# PowerSupply.net
KiCad netlist of a schematic drawn in Altium Designer
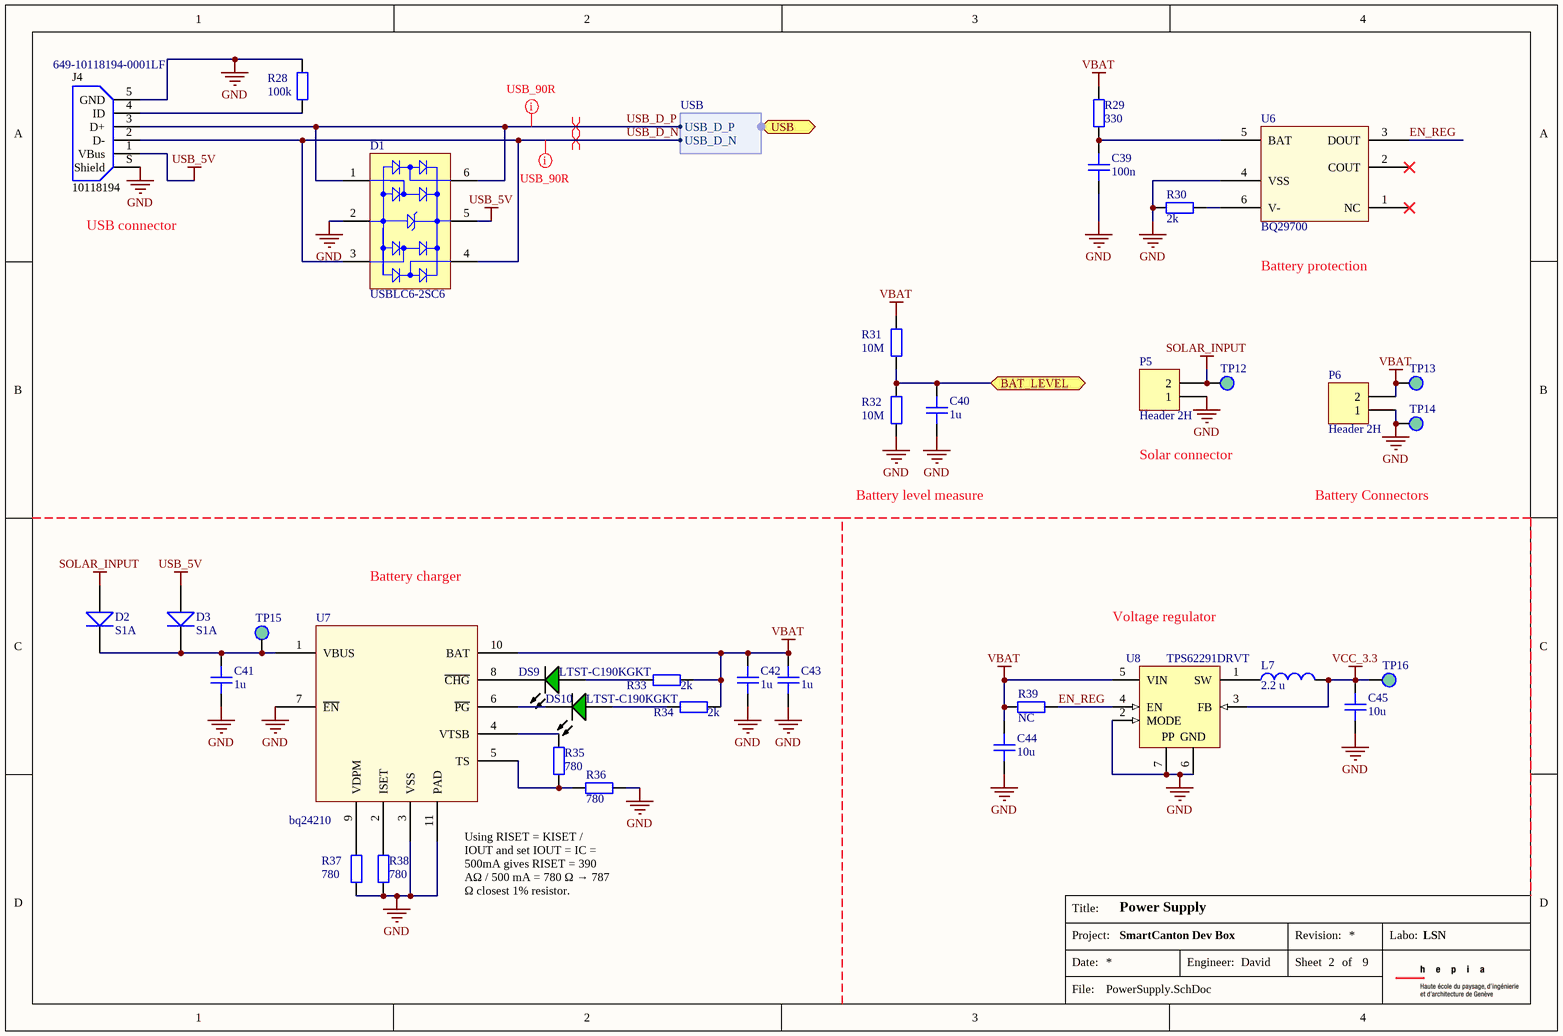
[diagram p0: PowerSupply.SchDoc]

(export (version "E")
  (design (tool "Eeschema 10.0.6"))
  (components
    (comp (ref "C39")
      (value "100n")
      (footprint "CAPC1608X08")
      (description "MLCC Capacitor 1608")
      (libsource (lib "HEPIA Vault") (part "CMP-001-0010-A.3"))
    )
    (comp (ref "C40")
      (value "1u")
      (footprint "CAPC1608X08")
      (description "MLCC Capacitor 1608")
      (libsource (lib "HEPIA Vault") (part "CMP-001-0010-A.3"))
    )
    (comp (ref "C41")
      (value "1u")
      (footprint "CAPC1608X08")
      (description "MLCC Capacitor 1608")
      (libsource (lib "HEPIA Vault") (part "CMP-001-0010-A.3"))
    )
    (comp (ref "C42")
      (value "1u")
      (footprint "CAPC1608X08")
      (description "MLCC Capacitor 1608")
      (libsource (lib "HEPIA Vault") (part "CMP-001-0010-A.3"))
    )
    (comp (ref "C43")
      (value "1u")
      (footprint "CAPC1608X08")
      (description "MLCC Capacitor 1608")
      (libsource (lib "HEPIA Vault") (part "CMP-001-0010-A.3"))
    )
    (comp (ref "C44")
      (value "10u")
      (footprint "CAPC2012X14")
      (description "MLCC Capacitor 2012")
      (libsource (lib "HEPIA Vault") (part "CMP-001-0011-A.3"))
    )
    (comp (ref "C45")
      (value "10u")
      (footprint "CAPC2012X14")
      (description "MLCC Capacitor 2012")
      (libsource (lib "HEPIA Vault") (part "CMP-001-0011-A.3"))
    )
    (comp (ref "D1")
      (value "USBLC6-2SC6")
      (footprint "STM-SOT23-6L_V")
      (description "Very low capacitance ESD protection, 3.5 pF, -40 to 125 degC, 6-Pin SOT23, RoHS, Tape and Reel")
      (fields (field (name "MANUFACTURER") "STMicroelectronics"))
      (libsource (lib "Altium Content Vault") (part "STM-USB_DVI_HDMIULC6-4SC6X-SOT23-6L"))
    )
    (comp (ref "D2")
      (value "S1A")
      (footprint "DO-214AC")
      (description "General-Purpose Rectifier, Vrrm = 50V")
      (libsource (lib "HEPIA Vault") (part "Diode"))
    )
    (comp (ref "D3")
      (value "S1A")
      (footprint "DO-214AC")
      (description "General-Purpose Rectifier, Vrrm = 50V")
      (libsource (lib "HEPIA Vault") (part "Diode"))
    )
    (comp (ref "DS9")
      (value "LTST-C190KGKT")
      (footprint "LITE-ON-LTST-C190GKT-2_V")
      (description "LED Uni-Color Green, 75 mW, 5 V, -30 to 85 degC, 2-Pin SMD, RoHS, Tape and Reel")
      (fields (field (name "MANUFACTURER") "Lite-On"))
      (libsource (lib "HEPIA Vault") (part "CMP-00026-A.1"))
    )
    (comp (ref "DS10")
      (value "LTST-C190KGKT")
      (footprint "LITE-ON-LTST-C190GKT-2_V")
      (description "LED Uni-Color Green, 75 mW, 5 V, -30 to 85 degC, 2-Pin SMD, RoHS, Tape and Reel")
      (fields (field (name "MANUFACTURER") "Lite-On"))
      (libsource (lib "HEPIA Vault") (part "LED_GREEN_A1K2-2"))
    )
    (comp (ref "J4")
      (value "10118194")
      (footprint "10118194-0001LF")
      (fields (field (name "SUPPLIER PART NUMBER 1") "649-10118194-0001LF"))
      (libsource (lib "HEPIA Vault") (part "CMP-001-0075-A.1"))
    )
    (comp (ref "L7")
      (value "2.2 u")
      (footprint "TDK-IND0805-125_V")
      (description "Multilayer Inductor, 2.2 uH, ±20%, 300 mOhm, 50MHz, 0805(2012)")
      (fields (field (name "PARTNUMBER") "MLZ2012N100LT"))
      (libsource (lib "Altium Content Vault") (part "CMP-0266-00001-1"))
    )
    (comp (ref "P5")
      (value "Header 2H")
      (footprint "HDR1X2H")
      (description "Header, 2-Pin, Right Angle")
      (fields (field (name "PUBLISHER") "Altium Limited"))
      (libsource (lib "Miscellaneous Connectors") (part "Header 2H"))
    )
    (comp (ref "P6")
      (value "Header 2H")
      (footprint "HDR1X2H")
      (description "Header, 2-Pin, Right Angle")
      (fields (field (name "PUBLISHER") "Altium Limited"))
      (libsource (lib "Miscellaneous Connectors") (part "Header 2H"))
    )
    (comp (ref "R28")
      (value "100k")
      (footprint "RESC1608X06")
      (description "1608 resistor")
      (libsource (lib "HEPIA Vault") (part "CMP-001-0005-A.4"))
    )
    (comp (ref "R29")
      (value "330")
      (footprint "RESC1608X06")
      (description "1608 resistor")
      (libsource (lib "HEPIA Vault") (part "CMP-001-0005-A.4"))
    )
    (comp (ref "R30")
      (value "2k")
      (footprint "RESC1608X06")
      (description "1608 resistor")
      (libsource (lib "") (part "CMP-001-0005-A.4_2"))
    )
    (comp (ref "R31")
      (value "10M")
      (footprint "RESC1608X06")
      (description "1608 resistor")
      (libsource (lib "HEPIA Vault") (part "CMP-001-0005-A.4"))
    )
    (comp (ref "R32")
      (value "10M")
      (footprint "RESC1608X06")
      (description "1608 resistor")
      (libsource (lib "HEPIA Vault") (part "CMP-001-0005-A.4"))
    )
    (comp (ref "R33")
      (value "2k")
      (footprint "RESC1608X06")
      (description "1608 resistor")
      (libsource (lib "") (part "CMP-001-0005-A.4_1"))
    )
    (comp (ref "R34")
      (value "2k")
      (footprint "RESC1608X06")
      (description "1608 resistor")
      (libsource (lib "") (part "CMP-001-0005-A.4_1"))
    )
    (comp (ref "R35")
      (value "780")
      (footprint "RESC1608X06")
      (description "1608 resistor")
      (libsource (lib "HEPIA Vault") (part "CMP-001-0005-A.4"))
    )
    (comp (ref "R36")
      (value "780")
      (footprint "RESC1608X06")
      (description "1608 resistor")
      (libsource (lib "") (part "CMP-001-0005-A.4_1"))
    )
    (comp (ref "R37")
      (value "780")
      (footprint "RESC1608X06")
      (description "1608 resistor")
      (libsource (lib "HEPIA Vault") (part "CMP-001-0005-A.4"))
    )
    (comp (ref "R38")
      (value "780")
      (footprint "RESC1608X06")
      (description "1608 resistor")
      (libsource (lib "HEPIA Vault") (part "CMP-001-0005-A.4"))
    )
    (comp (ref "R39")
      (value "NC")
      (footprint "RESC1608X06")
      (description "1608 resistor")
      (libsource (lib "") (part "CMP-001-0005-A.4_1"))
    )
    (comp (ref "TP12")
      (value "5015")
      (footprint "5015")
      (description "Circuit Board Hardware - PCB MINI SMT TEST POINT")
      (libsource (lib "HEPIA Vault") (part "CMP-001-0108-A.3"))
    )
    (comp (ref "TP13")
      (value "5015")
      (footprint "5015")
      (description "Circuit Board Hardware - PCB MINI SMT TEST POINT")
      (libsource (lib "HEPIA Vault") (part "CMP-001-0108-A.3"))
    )
    (comp (ref "TP14")
      (value "5015")
      (footprint "5015")
      (description "Circuit Board Hardware - PCB MINI SMT TEST POINT")
      (libsource (lib "HEPIA Vault") (part "CMP-001-0108-A.3"))
    )
    (comp (ref "TP15")
      (value "5015")
      (footprint "5015")
      (description "Circuit Board Hardware - PCB MINI SMT TEST POINT")
      (libsource (lib "HEPIA Vault") (part "CMP-001-0108-A.3"))
    )
    (comp (ref "TP16")
      (value "5015")
      (footprint "5015")
      (description "Circuit Board Hardware - PCB MINI SMT TEST POINT")
      (libsource (lib "HEPIA Vault") (part "CMP-001-0108-A.3"))
    )
    (comp (ref "U6")
      (value "BQ29700")
      (footprint "SON50P150X75-6M")
      (libsource (lib "HEPIA Vault") (part "bq297xx"))
    )
    (comp (ref "U7")
      (value "bq24210")
      (footprint "WSON50P200X300X80-11N")
      (description "800-mA, Single-Input, Single-Cell Li-Ion Battery Solar Charger")
      (libsource (lib "HEPIA Vault") (part "CMP-001-0111-A.1"))
    )
    (comp (ref "U8")
      (value "TPS62291DRVT")
      (footprint "DRV0006A_V")
      (fields (field (name "MANUFACTURER") "Texas Instruments"))
      (libsource (lib "HEPIA Vault") (part "TI-TPS62291DRV6-1600X1000TP"))
    )
  )
  (nets
    (net (code "2") (name "/BAT_LEVEL") (class "Default")
      (node (ref "C40") (pin "2") (pinfunction "2_2") (pintype "passive"))
      (node (ref "R31") (pin "1") (pinfunction "1_1") (pintype "passive"))
      (node (ref "R32") (pin "2") (pinfunction "2_2") (pintype "passive"))
    )
    (net (code "3") (name "/EN_REG") (class "Default")
      (node (ref "R39") (pin "1") (pinfunction "1_1") (pintype "passive"))
      (node (ref "U6") (pin "3") (pinfunction "DOUT_3") (pintype "passive"))
      (node (ref "U8") (pin "4") (pinfunction "EN_4") (pintype "input"))
    )
    (net (code "4") (name "/USB_D_N") (class "Default")
      (node (ref "D1") (pin "3") (pinfunction "I/O_2_3") (pintype "passive"))
      (node (ref "D1") (pin "4") (pinfunction "I/O_3_4") (pintype "passive"))
      (node (ref "J4") (pin "2") (pinfunction "D-_2") (pintype "passive"))
    )
    (net (code "5") (name "/USB_D_P") (class "Default")
      (node (ref "D1") (pin "1") (pinfunction "I/O_1_1") (pintype "passive"))
      (node (ref "D1") (pin "6") (pinfunction "I/O_4_6") (pintype "passive"))
      (node (ref "J4") (pin "3") (pinfunction "D+_3") (pintype "passive"))
    )
    (net (code "7") (name "GND") (class "Default")
      (node (ref "C39") (pin "1") (pinfunction "1_1") (pintype "passive"))
      (node (ref "C40") (pin "1") (pinfunction "1_1") (pintype "passive"))
      (node (ref "C41") (pin "1") (pinfunction "1_1") (pintype "passive"))
      (node (ref "C42") (pin "1") (pinfunction "1_1") (pintype "passive"))
      (node (ref "C43") (pin "1") (pinfunction "1_1") (pintype "passive"))
      (node (ref "C44") (pin "2") (pinfunction "2_2") (pintype "passive"))
      (node (ref "C45") (pin "2") (pinfunction "2_2") (pintype "passive"))
      (node (ref "D1") (pin "2") (pinfunction "GND_2") (pintype "passive"))
      (node (ref "J4") (pin "5") (pinfunction "GND_5") (pintype "passive"))
      (node (ref "J4") (pin "S") (pinfunction "Shield_S") (pintype "passive"))
      (node (ref "P5") (pin "1") (pinfunction "1_1") (pintype "passive"))
      (node (ref "P6") (pin "1") (pinfunction "1_1") (pintype "passive"))
      (node (ref "R28") (pin "2") (pinfunction "2_2") (pintype "passive"))
      (node (ref "R30") (pin "1") (pinfunction "1_1") (pintype "passive"))
      (node (ref "R32") (pin "1") (pinfunction "1_1") (pintype "passive"))
      (node (ref "R36") (pin "1") (pinfunction "1_1") (pintype "passive"))
      (node (ref "R37") (pin "1") (pinfunction "1_1") (pintype "passive"))
      (node (ref "R38") (pin "1") (pinfunction "1_1") (pintype "passive"))
      (node (ref "TP14") (pin "1") (pinfunction "TP_1") (pintype "passive"))
      (node (ref "U6") (pin "4") (pinfunction "VSS_4") (pintype "passive"))
      (node (ref "U7") (pin "11") (pinfunction "PAD_11") (pintype "passive"))
      (node (ref "U7") (pin "3") (pinfunction "VSS_3") (pintype "passive"))
      (node (ref "U7") (pin "7") (pinfunction "~{EN}_7") (pintype "passive"))
      (node (ref "U8") (pin "2") (pinfunction "MODE_2") (pintype "input"))
      (node (ref "U8") (pin "6") (pinfunction "GND_6") (pintype "power_in"))
      (node (ref "U8") (pin "7") (pinfunction "EP_7") (pintype "passive"))
    )
    (net (code "8") (name "Net-(DS9-A)") (class "Default")
      (node (ref "DS9") (pin "1") (pinfunction "A_1") (pintype "passive"))
      (node (ref "R33") (pin "2") (pinfunction "2_2") (pintype "passive"))
    )
    (net (code "9") (name "Net-(DS9-K)") (class "Default")
      (node (ref "DS9") (pin "2") (pinfunction "K_2") (pintype "passive"))
      (node (ref "U7") (pin "8") (pinfunction "~{CHG}_8") (pintype "passive"))
    )
    (net (code "10") (name "Net-(DS10-A)") (class "Default")
      (node (ref "DS10") (pin "1") (pinfunction "A_1") (pintype "passive"))
      (node (ref "R34") (pin "2") (pinfunction "2_2") (pintype "passive"))
    )
    (net (code "11") (name "Net-(DS10-K)") (class "Default")
      (node (ref "DS10") (pin "2") (pinfunction "K_2") (pintype "passive"))
      (node (ref "U7") (pin "6") (pinfunction "~{PG}_6") (pintype "passive"))
    )
    (net (code "12") (name "Net-(J4-ID)") (class "Default")
      (node (ref "J4") (pin "4") (pinfunction "ID_4") (pintype "passive"))
      (node (ref "R28") (pin "1") (pinfunction "1_1") (pintype "passive"))
    )
    (net (code "13") (name "Net-(TP15-TP)") (class "Default")
      (node (ref "C41") (pin "2") (pinfunction "2_2") (pintype "passive"))
      (node (ref "D2") (pin "K") (pinfunction "K_K") (pintype "passive"))
      (node (ref "D3") (pin "K") (pinfunction "K_K") (pintype "passive"))
      (node (ref "TP15") (pin "1") (pinfunction "TP_1") (pintype "passive"))
      (node (ref "U7") (pin "1") (pinfunction "VBUS_1") (pintype "passive"))
    )
    (net (code "14") (name "Net-(U6-BAT)") (class "Default")
      (node (ref "C39") (pin "2") (pinfunction "2_2") (pintype "passive"))
      (node (ref "R29") (pin "1") (pinfunction "1_1") (pintype "passive"))
      (node (ref "U6") (pin "5") (pinfunction "BAT_5") (pintype "passive"))
    )
    (net (code "15") (name "Net-(U6-V-)") (class "Default")
      (node (ref "R30") (pin "2") (pinfunction "2_2") (pintype "passive"))
      (node (ref "U6") (pin "6") (pinfunction "V-_6") (pintype "passive"))
    )
    (net (code "16") (name "Net-(U7-ISET)") (class "Default")
      (node (ref "R38") (pin "2") (pinfunction "2_2") (pintype "passive"))
      (node (ref "U7") (pin "2") (pinfunction "ISET_2") (pintype "passive"))
    )
    (net (code "17") (name "Net-(U7-TS)") (class "Default")
      (node (ref "R35") (pin "1") (pinfunction "1_1") (pintype "passive"))
      (node (ref "R36") (pin "2") (pinfunction "2_2") (pintype "passive"))
      (node (ref "U7") (pin "5") (pinfunction "TS_5") (pintype "passive"))
    )
    (net (code "18") (name "Net-(U7-VDPM)") (class "Default")
      (node (ref "R37") (pin "2") (pinfunction "2_2") (pintype "passive"))
      (node (ref "U7") (pin "9") (pinfunction "VDPM_9") (pintype "passive"))
    )
    (net (code "19") (name "Net-(U7-VTSB)") (class "Default")
      (node (ref "R35") (pin "2") (pinfunction "2_2") (pintype "passive"))
      (node (ref "U7") (pin "4") (pinfunction "VTSB_4") (pintype "passive"))
    )
    (net (code "20") (name "Net-(U8-SW)") (class "Default")
      (node (ref "L7") (pin "1") (pinfunction "1_1") (pintype "passive"))
      (node (ref "U8") (pin "1") (pinfunction "SW_1") (pintype "power_in"))
    )
    (net (code "21") (name "SOLAR_INPUT") (class "Default")
      (node (ref "D2") (pin "A") (pinfunction "A_A") (pintype "passive"))
      (node (ref "P5") (pin "2") (pinfunction "2_2") (pintype "passive"))
      (node (ref "TP12") (pin "1") (pinfunction "TP_1") (pintype "passive"))
    )
    (net (code "22") (name "USB_5V") (class "Default")
      (node (ref "D1") (pin "5") (pinfunction "VBUS_5") (pintype "passive"))
      (node (ref "D3") (pin "A") (pinfunction "A_A") (pintype "passive"))
      (node (ref "J4") (pin "1") (pinfunction "VBus_1") (pintype "passive"))
    )
    (net (code "23") (name "VBAT") (class "Default")
      (node (ref "C42") (pin "2") (pinfunction "2_2") (pintype "passive"))
      (node (ref "C43") (pin "2") (pinfunction "2_2") (pintype "passive"))
      (node (ref "C44") (pin "1") (pinfunction "1_1") (pintype "passive"))
      (node (ref "P6") (pin "2") (pinfunction "2_2") (pintype "passive"))
      (node (ref "R29") (pin "2") (pinfunction "2_2") (pintype "passive"))
      (node (ref "R31") (pin "2") (pinfunction "2_2") (pintype "passive"))
      (node (ref "R33") (pin "1") (pinfunction "1_1") (pintype "passive"))
      (node (ref "R34") (pin "1") (pinfunction "1_1") (pintype "passive"))
      (node (ref "R39") (pin "2") (pinfunction "2_2") (pintype "passive"))
      (node (ref "TP13") (pin "1") (pinfunction "TP_1") (pintype "passive"))
      (node (ref "U7") (pin "10") (pinfunction "BAT_10") (pintype "passive"))
      (node (ref "U8") (pin "5") (pinfunction "VIN_5") (pintype "power_in"))
    )
    (net (code "24") (name "VCC_3.3") (class "Default")
      (node (ref "C45") (pin "1") (pinfunction "1_1") (pintype "passive"))
      (node (ref "L7") (pin "2") (pinfunction "2_2") (pintype "passive"))
      (node (ref "TP16") (pin "1") (pinfunction "TP_1") (pintype "passive"))
      (node (ref "U8") (pin "3") (pinfunction "FB_3") (pintype "input"))
    )
    (net (code "25") (name "unconnected-(U6-COUT-Pad2)") (class "Default")
      (node (ref "U6") (pin "2") (pinfunction "COUT_2") (pintype "passive+no_connect"))
    )
    (net (code "26") (name "unconnected-(U6-NC-Pad1)") (class "Default")
      (node (ref "U6") (pin "1") (pinfunction "NC_1") (pintype "passive+no_connect"))
    )
  )
)
